# mon.net
KiCad netlist of a schematic drawn in EAGLE
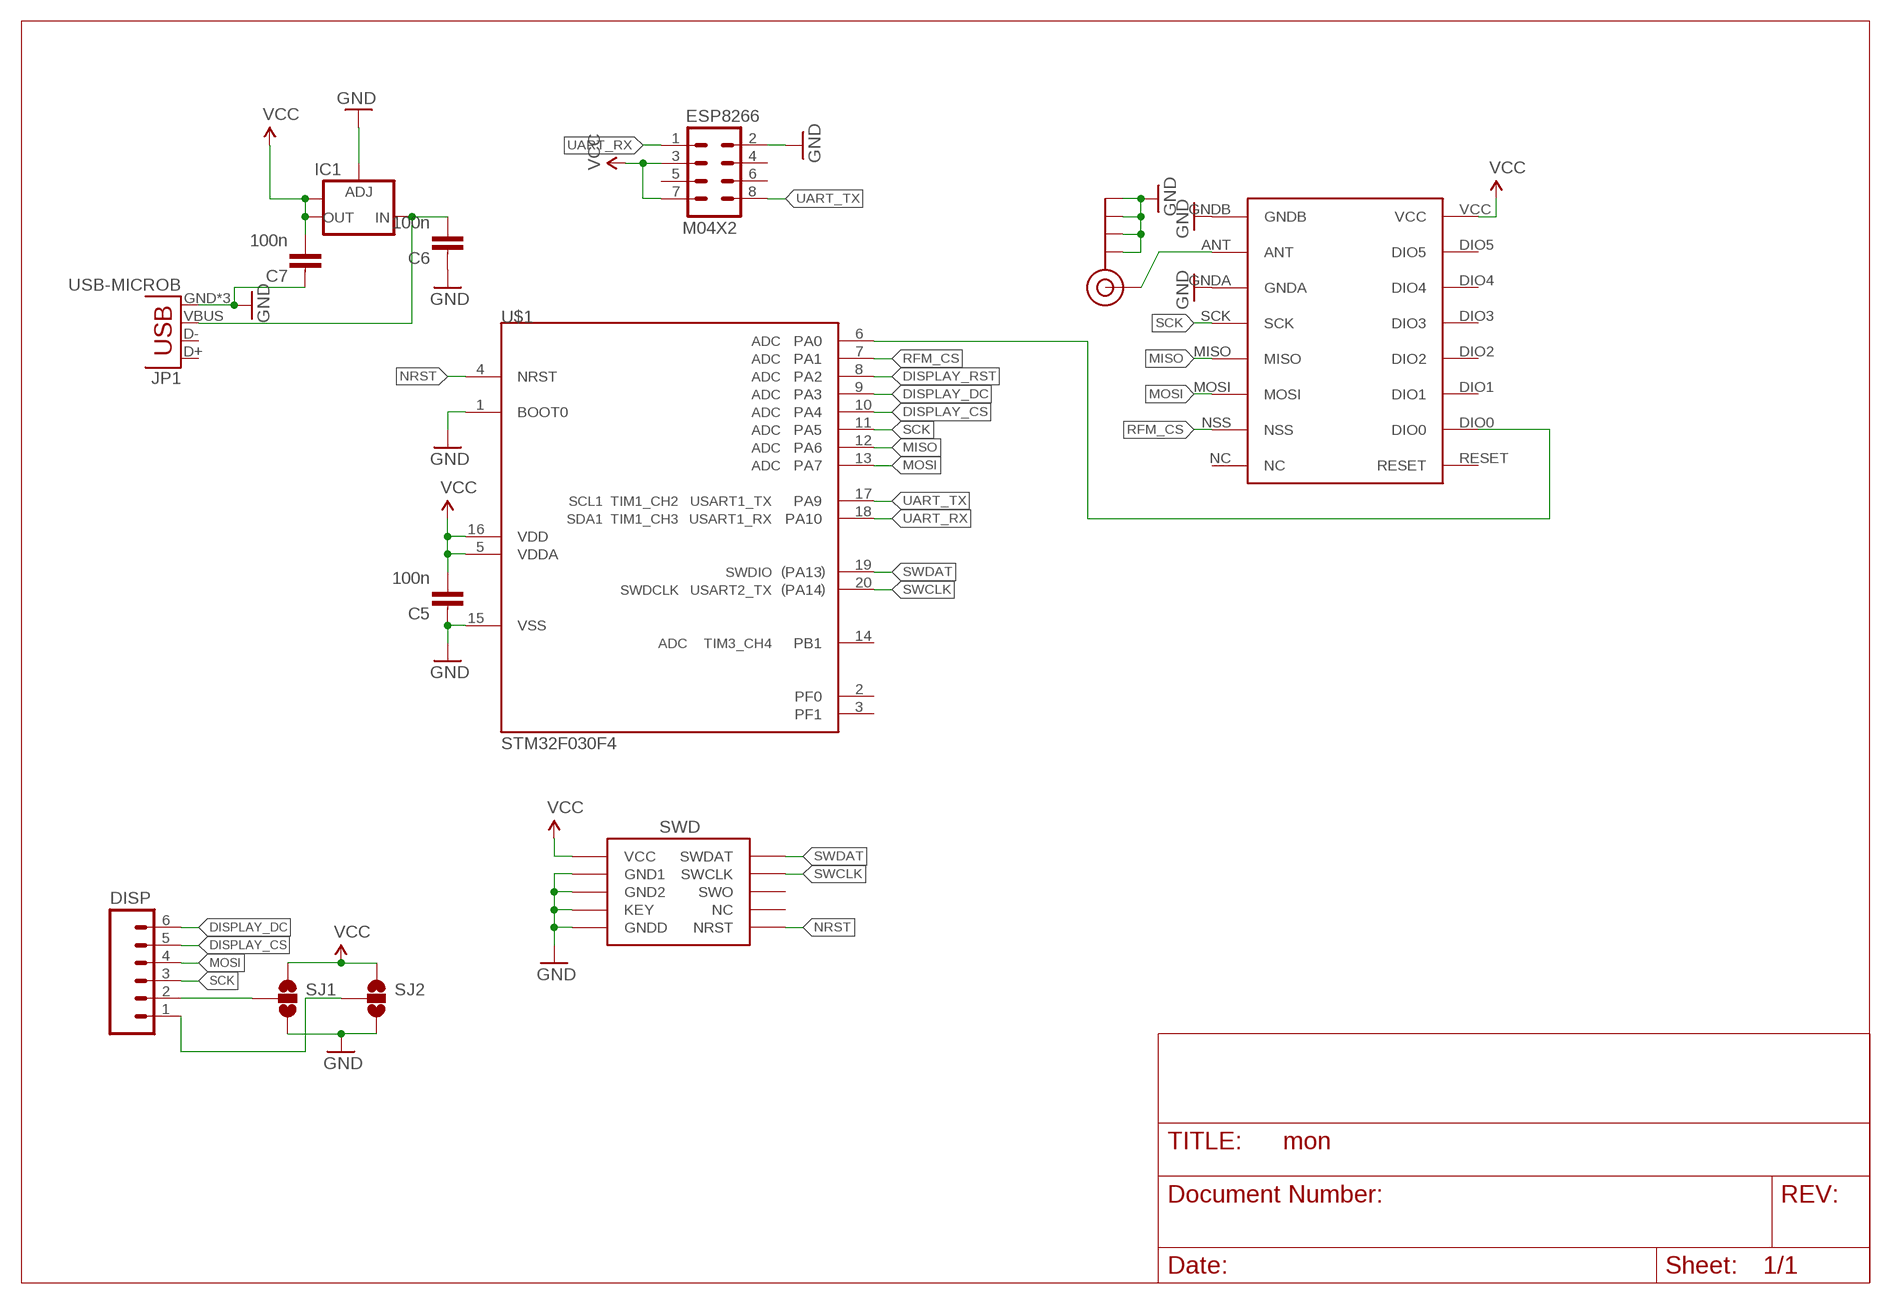
[diagram p0: schematic, sheet 1]

(export (version "E")
  (design (tool "Eeschema 10.0.6"))
  (components
    (comp (ref "C5")
      (value "100n")
      (footprint "eagle-import:C0603-L")
      (libsource (lib "eagle-import") (part "CAPACITOR0603-L"))
    )
    (comp (ref "C6")
      (value "100n")
      (footprint "eagle-import:C0603-L")
      (libsource (lib "eagle-import") (part "CAPACITOR0603-L"))
    )
    (comp (ref "C7")
      (value "100n")
      (footprint "eagle-import:C0603-L")
      (libsource (lib "eagle-import") (part "CAPACITOR0603-L"))
    )
    (comp (ref "DISP")
      (value "M06SILK_FEMALE_PTH")
      (footprint "eagle-import:1X06")
      (libsource (lib "eagle-import") (part "M06SILK_FEMALE_PTH"))
    )
    (comp (ref "ESP8266")
      (value "M04X2")
      (footprint "eagle-import:2X4")
      (libsource (lib "eagle-import") (part "M04X2"))
    )
    (comp (ref "IC1")
      (value "V_REG_LM1117SOT223")
      (footprint "eagle-import:SOT223")
      (libsource (lib "eagle-import") (part "V_REG_LM1117SOT223"))
    )
    (comp (ref "J$1")
      (value "SMA_EDGE")
      (footprint "eagle-import:SMA-EDGE")
      (libsource (lib "eagle-import") (part "SMA_EDGE"))
    )
    (comp (ref "JP1")
      (value "USB-MICROB")
      (footprint "eagle-import:USB-MICROB")
      (libsource (lib "eagle-import") (part "USB-MICROB"))
    )
    (comp (ref "SJ1")
      (value "SOLDERJUMPER_2WAYS")
      (footprint "eagle-import:SJ_3")
      (libsource (lib "eagle-import") (part "SOLDERJUMPER_2WAYS"))
    )
    (comp (ref "SJ2")
      (value "SOLDERJUMPER_2WAYS")
      (footprint "eagle-import:SJ_3")
      (libsource (lib "eagle-import") (part "SOLDERJUMPER_2WAYS"))
    )
    (comp (ref "U$1")
      (value "STM32F030F4")
      (footprint "eagle-import:TSSOP20")
      (libsource (lib "eagle-import") (part "STM32F030F4"))
    )
    (comp (ref "U$2")
      (value "RFM69HW")
      (footprint "eagle-import:RFM")
      (libsource (lib "eagle-import") (part "RFM69HW"))
    )
    (comp (ref "U$4")
      (value "SWD_SHROUD_SMD")
      (footprint "eagle-import:SWD_SMD_SHROUD")
      (libsource (lib "eagle-import") (part "SWD_SHROUD_SMD"))
    )
  )
  (nets
    (net (code "1") (name "DISPLAY_CS") (class "Default")
      (node (ref "DISP") (pin "5") (pinfunction "5_5") (pintype "passive"))
      (node (ref "U$1") (pin "10") (pinfunction "PA4_10") (pintype "bidirectional"))
    )
    (net (code "2") (name "DISPLAY_DC") (class "Default")
      (node (ref "DISP") (pin "6") (pinfunction "6_6") (pintype "passive"))
      (node (ref "U$1") (pin "9") (pinfunction "PA3_9") (pintype "bidirectional"))
    )
    (net (code "3") (name "DISPLAY_RST") (class "Default")
      (node (ref "U$1") (pin "8") (pinfunction "PA2_8") (pintype "bidirectional"))
    )
    (net (code "4") (name "GND") (class "Default")
      (node (ref "C5") (pin "1") (pinfunction "1_1") (pintype "passive"))
      (node (ref "C6") (pin "1") (pinfunction "1_1") (pintype "passive"))
      (node (ref "C7") (pin "1") (pinfunction "1_1") (pintype "passive"))
      (node (ref "ESP8266") (pin "2") (pinfunction "2_2") (pintype "passive"))
      (node (ref "IC1") (pin "1") (pinfunction "ADJ_1") (pintype "input"))
      (node (ref "J$1") (pin "GND@0") (pinfunction "GND_GND@0") (pintype "bidirectional"))
      (node (ref "J$1") (pin "GND@1") (pinfunction "GND_GND@1") (pintype "bidirectional"))
      (node (ref "J$1") (pin "GND@2") (pinfunction "GND_GND@2") (pintype "bidirectional"))
      (node (ref "J$1") (pin "GND@3") (pinfunction "GND_GND@3") (pintype "bidirectional"))
      (node (ref "JP1") (pin "GND") (pinfunction "GND_GND") (pintype "bidirectional"))
      (node (ref "JP1") (pin "MT1") (pinfunction "GND_MT1") (pintype "bidirectional"))
      (node (ref "JP1") (pin "MT2") (pinfunction "GND_MT2") (pintype "bidirectional"))
      (node (ref "SJ1") (pin "3") (pinfunction "3_3") (pintype "passive"))
      (node (ref "SJ2") (pin "3") (pinfunction "3_3") (pintype "passive"))
      (node (ref "U$1") (pin "1") (pinfunction "BOOT0_1") (pintype "input"))
      (node (ref "U$1") (pin "15") (pinfunction "VSS_15") (pintype "power_in"))
      (node (ref "U$2") (pin "GNDA") (pinfunction "GNDA_GNDA") (pintype "bidirectional"))
      (node (ref "U$2") (pin "GNDB") (pinfunction "GNDB_GNDB") (pintype "bidirectional"))
      (node (ref "U$4") (pin "3") (pinfunction "GND1_3") (pintype "power_in"))
      (node (ref "U$4") (pin "5") (pinfunction "GND2_5") (pintype "power_in"))
      (node (ref "U$4") (pin "7") (pinfunction "KEY_7") (pintype "bidirectional"))
      (node (ref "U$4") (pin "9") (pinfunction "GNDD_9") (pintype "power_in"))
    )
    (net (code "5") (name "MISO") (class "Default")
      (node (ref "U$1") (pin "12") (pinfunction "PA6_12") (pintype "bidirectional"))
      (node (ref "U$2") (pin "MISO") (pinfunction "MISO_MISO") (pintype "bidirectional"))
    )
    (net (code "6") (name "MOSI") (class "Default")
      (node (ref "DISP") (pin "4") (pinfunction "4_4") (pintype "passive"))
      (node (ref "U$1") (pin "13") (pinfunction "PA7_13") (pintype "bidirectional"))
      (node (ref "U$2") (pin "MOSI") (pinfunction "MOSI_MOSI") (pintype "bidirectional"))
    )
    (net (code "7") (name "NRST") (class "Default")
      (node (ref "U$1") (pin "4") (pinfunction "NRST_4") (pintype "input"))
      (node (ref "U$4") (pin "10") (pinfunction "NRST_10") (pintype "bidirectional"))
    )
    (net (code "8") (name "Net-(DISP-Pad1)") (class "Default")
      (node (ref "DISP") (pin "1") (pinfunction "1_1") (pintype "passive"))
      (node (ref "SJ2") (pin "2") (pinfunction "2_2") (pintype "passive"))
    )
    (net (code "9") (name "Net-(DISP-Pad2)") (class "Default")
      (node (ref "DISP") (pin "2") (pinfunction "2_2") (pintype "passive"))
      (node (ref "SJ1") (pin "2") (pinfunction "2_2") (pintype "passive"))
    )
    (net (code "10") (name "Net-(IC1-IN)") (class "Default")
      (node (ref "C6") (pin "2") (pinfunction "2_2") (pintype "passive"))
      (node (ref "IC1") (pin "3") (pinfunction "IN_3") (pintype "input"))
      (node (ref "JP1") (pin "VBUS") (pinfunction "VBUS_VBUS") (pintype "bidirectional"))
    )
    (net (code "11") (name "Net-(J$1-SIGNAL)") (class "Default")
      (node (ref "J$1") (pin "SIG") (pinfunction "SIGNAL_SIG") (pintype "bidirectional"))
      (node (ref "U$2") (pin "ANT") (pinfunction "ANT_ANT") (pintype "bidirectional"))
    )
    (net (code "12") (name "Net-(U$1-PA0)") (class "Default")
      (node (ref "U$1") (pin "6") (pinfunction "PA0_6") (pintype "bidirectional"))
      (node (ref "U$2") (pin "DIO0") (pinfunction "DIO0_DIO0") (pintype "bidirectional"))
    )
    (net (code "13") (name "RFM_CS") (class "Default")
      (node (ref "U$1") (pin "7") (pinfunction "PA1_7") (pintype "bidirectional"))
      (node (ref "U$2") (pin "NSS") (pinfunction "NSS_NSS") (pintype "bidirectional"))
    )
    (net (code "14") (name "SCK") (class "Default")
      (node (ref "DISP") (pin "3") (pinfunction "3_3") (pintype "passive"))
      (node (ref "U$1") (pin "11") (pinfunction "PA5_11") (pintype "bidirectional"))
      (node (ref "U$2") (pin "SCK") (pinfunction "SCK_SCK") (pintype "bidirectional"))
    )
    (net (code "15") (name "SWCLK") (class "Default")
      (node (ref "U$1") (pin "20") (pinfunction "PA14_20") (pintype "bidirectional"))
      (node (ref "U$4") (pin "4") (pinfunction "SWCLK_4") (pintype "bidirectional"))
    )
    (net (code "16") (name "SWDAT") (class "Default")
      (node (ref "U$1") (pin "19") (pinfunction "PA13_19") (pintype "bidirectional"))
      (node (ref "U$4") (pin "2") (pinfunction "SWDAT_2") (pintype "bidirectional"))
    )
    (net (code "17") (name "UART_RX") (class "Default")
      (node (ref "ESP8266") (pin "1") (pinfunction "1_1") (pintype "passive"))
      (node (ref "U$1") (pin "18") (pinfunction "PA10_18") (pintype "bidirectional"))
    )
    (net (code "18") (name "UART_TX") (class "Default")
      (node (ref "ESP8266") (pin "8") (pinfunction "8_8") (pintype "passive"))
      (node (ref "U$1") (pin "17") (pinfunction "PA9_17") (pintype "bidirectional"))
    )
    (net (code "19") (name "VCC") (class "Default")
      (node (ref "C5") (pin "2") (pinfunction "2_2") (pintype "passive"))
      (node (ref "C7") (pin "2") (pinfunction "2_2") (pintype "passive"))
      (node (ref "ESP8266") (pin "3") (pinfunction "3_3") (pintype "passive"))
      (node (ref "ESP8266") (pin "7") (pinfunction "7_7") (pintype "passive"))
      (node (ref "IC1") (pin "2") (pinfunction "OUT_2") (pintype "output"))
      (node (ref "IC1") (pin "4") (pinfunction "OUT_4") (pintype "output"))
      (node (ref "SJ1") (pin "1") (pinfunction "1_1") (pintype "passive"))
      (node (ref "SJ2") (pin "1") (pinfunction "1_1") (pintype "passive"))
      (node (ref "U$1") (pin "16") (pinfunction "VDD_16") (pintype "power_in"))
      (node (ref "U$1") (pin "5") (pinfunction "VDDA_5") (pintype "power_in"))
      (node (ref "U$2") (pin "VCC") (pinfunction "VCC_VCC") (pintype "bidirectional"))
      (node (ref "U$4") (pin "1") (pinfunction "VCC_1") (pintype "power_in"))
    )
    (net (code "20") (name "unconnected-(ESP8266-Pad4)") (class "Default")
      (node (ref "ESP8266") (pin "4") (pinfunction "4_4") (pintype "passive"))
    )
    (net (code "21") (name "unconnected-(ESP8266-Pad5)") (class "Default")
      (node (ref "ESP8266") (pin "5") (pinfunction "5_5") (pintype "passive"))
    )
    (net (code "22") (name "unconnected-(ESP8266-Pad6)") (class "Default")
      (node (ref "ESP8266") (pin "6") (pinfunction "6_6") (pintype "passive"))
    )
    (net (code "23") (name "unconnected-(JP1-PadD+)") (class "Default")
      (node (ref "JP1") (pin "D+") (pinfunction "D+_D+") (pintype "bidirectional"))
    )
    (net (code "24") (name "unconnected-(JP1-PadD-)") (class "Default")
      (node (ref "JP1") (pin "D-") (pinfunction "D-_D-") (pintype "bidirectional"))
    )
    (net (code "25") (name "unconnected-(U$1-PB1-Pad14)") (class "Default")
      (node (ref "U$1") (pin "14") (pinfunction "PB1_14") (pintype "bidirectional"))
    )
    (net (code "26") (name "unconnected-(U$1-PF0-Pad2)") (class "Default")
      (node (ref "U$1") (pin "2") (pinfunction "PF0_2") (pintype "bidirectional"))
    )
    (net (code "27") (name "unconnected-(U$1-PF1-Pad3)") (class "Default")
      (node (ref "U$1") (pin "3") (pinfunction "PF1_3") (pintype "bidirectional"))
    )
    (net (code "28") (name "unconnected-(U$2-PadDIO1)") (class "Default")
      (node (ref "U$2") (pin "DIO1") (pinfunction "DIO1_DIO1") (pintype "bidirectional"))
    )
    (net (code "29") (name "unconnected-(U$2-PadDIO2)") (class "Default")
      (node (ref "U$2") (pin "DIO2") (pinfunction "DIO2_DIO2") (pintype "bidirectional"))
    )
    (net (code "30") (name "unconnected-(U$2-PadDIO3)") (class "Default")
      (node (ref "U$2") (pin "DIO3") (pinfunction "DIO3_DIO3") (pintype "bidirectional"))
    )
    (net (code "31") (name "unconnected-(U$2-PadDIO4)") (class "Default")
      (node (ref "U$2") (pin "DIO4") (pinfunction "DIO4_DIO4") (pintype "bidirectional"))
    )
    (net (code "32") (name "unconnected-(U$2-PadDIO5)") (class "Default")
      (node (ref "U$2") (pin "DIO5") (pinfunction "DIO5_DIO5") (pintype "bidirectional"))
    )
    (net (code "33") (name "unconnected-(U$2-PadNC)") (class "Default")
      (node (ref "U$2") (pin "NC") (pinfunction "NC_NC") (pintype "bidirectional"))
    )
    (net (code "34") (name "unconnected-(U$2-PadRESET)") (class "Default")
      (node (ref "U$2") (pin "RESET") (pinfunction "RESET_RESET") (pintype "bidirectional"))
    )
    (net (code "35") (name "unconnected-(U$4-NC-Pad8)") (class "Default")
      (node (ref "U$4") (pin "8") (pinfunction "NC_8") (pintype "no_connect"))
    )
    (net (code "36") (name "unconnected-(U$4-SWO-Pad6)") (class "Default")
      (node (ref "U$4") (pin "6") (pinfunction "SWO_6") (pintype "bidirectional"))
    )
  )
)
